# MSXII_SteeringWheelRightBoard.net
KiCad netlist of a schematic drawn in Altium Designer
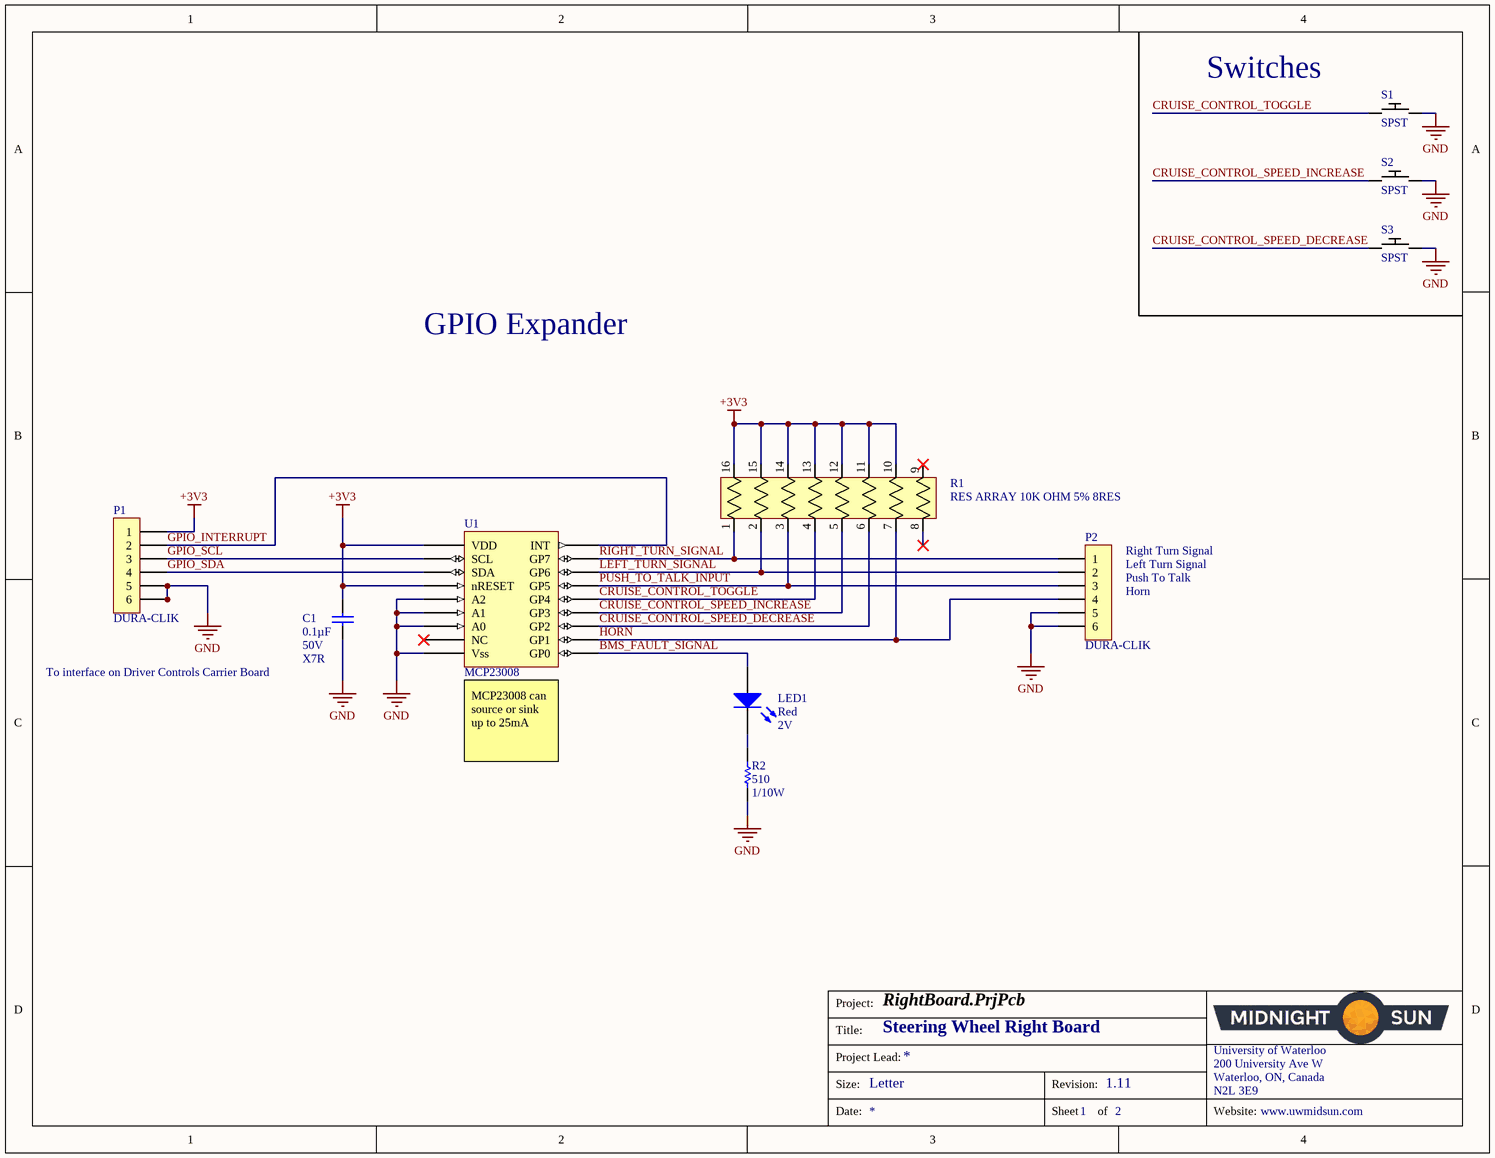
[diagram p0: MSXII_SteeringWheelRightBoard.SchDoc]

(export (version "E")
  (design (tool "Eeschema 10.0.6"))
  (components
    (comp (ref "C1")
      (value "CAP CER 0.1UF 50V 10% X7R 0603")
      (footprint "CAP, 0603")
      (description "0.10µF ±10% 50V Ceramic Capacitor X7R 0603 (1608 Metric)")
      (fields
        (field (name "TOLERANCE") "±10%")
        (field (name "CAPACITANCE") "0.1µF")
        (field (name "VOLTAGE") "50V")
        (field (name "TEMPERATURE COEFFICIENT") "X7R")
      )
      (libsource (lib "Schematic Diagrams") (part "CAP CER 0.1UF 50V 10% X7R 0603"))
    )
    (comp (ref "LED1")
      (value "LED RED CLEAR 2V 0603")
      (footprint "LED_0603")
      (description "Red 631nm LED Indication - Discrete 2V 0603 (1608 Metric)")
      (fields
        (field (name "MANUFACTURER") "Wurth Electronics Inc.")
        (field (name "MANUFACTURER PART NUMBER") "150060RS75000")
        (field (name "COLOR") "Red")
        (field (name "VOLTAGE - FORWARD (VF) (TYP)") "2V")
      )
      (libsource (lib "Schematic Diagrams") (part "LED RED CLEAR 2V 0603"))
    )
    (comp (ref "P1")
      (value "DURA-CLIK")
      (footprint "CONN, 6POS DURA-CLIK VERT")
      (description "6 Positions Header, Shrouded Connector 0.079\" (2.00mm) Surface Mount, Vertical Tin")
      (fields (field (name "MANUFACTURER") "Molex") (field (name "MANUFACTURER PART NUMBER") "5600200820"))
      (libsource (lib "") (part "CONN 6POS DURA-CLIK 0.079{dblquote}_1"))
    )
    (comp (ref "P2")
      (value "DURA-CLIK")
      (footprint "CONN, 6POS DURA-CLIK VERT")
      (description "6 Positions Header, Shrouded Connector 0.079\" (2.00mm) Surface Mount, Vertical Tin")
      (fields (field (name "MANUFACTURER") "Molex") (field (name "MANUFACTURER PART NUMBER") "5600200820"))
      (libsource (lib "Schematic Diagrams") (part "CONN 6POS DURA-CLIK 0.079{dblquote}"))
    )
    (comp (ref "R1")
      (value "RES ARRAY 10K OHM 5% 8RES")
      (footprint "RES ARRAY, 8 POS 1506")
      (description "RES ARRAY SMD 10K 5% 62.5mW 1506")
      (fields
        (field (name "MANUFACTURER_PART_NUMBER") "EXB-2HV103JV")
        (field (name "MANUFACTURER") "Panasonic Electronic Components")
        (field (name "COPYRIGHT") "Copyright (C) 2015 Accelerated Designs. All rights reserved")
      )
      (libsource (lib "Schematic Diagrams") (part "RES ARRAY 10K OHM 5% 8RES EXB-2HV103JV"))
    )
    (comp (ref "R2")
      (value "RES 510 OHM 5% 1/10W 0603")
      (footprint "RES, 0603")
      (description "RES SMD 510 OHM 5% 1/10W 0603")
      (fields
        (field (name "TOLERANCE") "±5%")
        (field (name "RESISTANCE") "510")
        (field (name "POWER") "1/10W")
      )
      (libsource (lib "Schematic Diagrams") (part "RES 510 OHM 5% 1/10W 0603"))
    )
    (comp (ref "S1")
      (value "SPST")
      (footprint "SW SPST D6 SERIES")
      (description "Pushbutton Switch SPST-NO Keyswitch Through Hole D6 Series")
      (fields (field (name "MANUFACTURER") "C&K") (field (name "MANUFACTURER PART NUMBER") "D6R00 F2 LFS"))
      (libsource (lib "Schematic Diagrams") (part "SW SPST-NO 0.1A 32V D6 Series"))
    )
    (comp (ref "S2")
      (value "SPST")
      (footprint "SW SPST D6 SERIES")
      (description "Pushbutton Switch SPST-NO Keyswitch Through Hole D6 Series")
      (fields (field (name "MANUFACTURER") "C&K") (field (name "MANUFACTURER PART NUMBER") "D6R00 F2 LFS"))
      (libsource (lib "Schematic Diagrams") (part "SW SPST-NO 0.1A 32V D6 Series"))
    )
    (comp (ref "S3")
      (value "SPST")
      (footprint "SW SPST D6 SERIES")
      (description "Pushbutton Switch SPST-NO Keyswitch Through Hole D6 Series")
      (fields (field (name "MANUFACTURER") "C&K") (field (name "MANUFACTURER PART NUMBER") "D6R00 F2 LFS"))
      (libsource (lib "Schematic Diagrams") (part "SW SPST-NO 0.1A 32V D6 Series"))
    )
    (comp (ref "U1")
      (value "MCP23008")
      (footprint "IC 18SOIC")
      (description "MCP23008 I/O Expander 8B+1Int 18P SOIC")
      (fields
        (field (name "MANUFACTURER") "Microchip Technology")
        (field (name "MANUFACTURER PART NUMBER") "MCP23008T-E/SO")
      )
      (libsource (lib "Schematic Diagrams") (part "IC I/O EXPANDER I2C 8B 18SOIC"))
    )
  )
  (nets
    (net (code "1") (name "+3V3") (class "Default")
      (node (ref "C1") (pin "1") (pinfunction "1_1") (pintype "passive"))
      (node (ref "P1") (pin "1") (pinfunction "1_1") (pintype "passive"))
      (node (ref "R1") (pin "10") (pinfunction "10_10") (pintype "passive"))
      (node (ref "R1") (pin "11") (pinfunction "11_11") (pintype "passive"))
      (node (ref "R1") (pin "12") (pinfunction "12_12") (pintype "passive"))
      (node (ref "R1") (pin "13") (pinfunction "13_13") (pintype "passive"))
      (node (ref "R1") (pin "14") (pinfunction "14_14") (pintype "passive"))
      (node (ref "R1") (pin "15") (pinfunction "15_15") (pintype "passive"))
      (node (ref "R1") (pin "16") (pinfunction "16_16") (pintype "passive"))
      (node (ref "U1") (pin "18") (pinfunction "VDD_18") (pintype "power_in"))
      (node (ref "U1") (pin "6") (pinfunction "nRESET_6") (pintype "input"))
    )
    (net (code "2") (name "/BMS_FAULT_SIGNAL") (class "Default")
      (node (ref "LED1") (pin "1") (pinfunction "A_1") (pintype "passive"))
      (node (ref "U1") (pin "10") (pinfunction "GP0_10") (pintype "bidirectional"))
    )
    (net (code "3") (name "/CRUISE_CONTROL_SPEED_DECREASE") (class "Default")
      (node (ref "R1") (pin "6") (pinfunction "6_6") (pintype "passive"))
      (node (ref "S3") (pin "1") (pinfunction "1_1") (pintype "passive"))
      (node (ref "U1") (pin "12") (pinfunction "GP2_12") (pintype "bidirectional"))
    )
    (net (code "4") (name "/CRUISE_CONTROL_SPEED_INCREASE") (class "Default")
      (node (ref "R1") (pin "5") (pinfunction "5_5") (pintype "passive"))
      (node (ref "S2") (pin "1") (pinfunction "1_1") (pintype "passive"))
      (node (ref "U1") (pin "13") (pinfunction "GP3_13") (pintype "bidirectional"))
    )
    (net (code "5") (name "/CRUISE_CONTROL_TOGGLE") (class "Default")
      (node (ref "R1") (pin "4") (pinfunction "4_4") (pintype "passive"))
      (node (ref "S1") (pin "1") (pinfunction "1_1") (pintype "passive"))
      (node (ref "U1") (pin "14") (pinfunction "GP4_14") (pintype "bidirectional"))
    )
    (net (code "6") (name "/GPIO_INTERRUPT") (class "Default")
      (node (ref "P1") (pin "2") (pinfunction "2_2") (pintype "passive"))
      (node (ref "U1") (pin "8") (pinfunction "INT_8") (pintype "output"))
    )
    (net (code "7") (name "/GPIO_SCL") (class "Default")
      (node (ref "P1") (pin "3") (pinfunction "3_3") (pintype "passive"))
      (node (ref "U1") (pin "1") (pinfunction "SCL_1") (pintype "bidirectional"))
    )
    (net (code "8") (name "/GPIO_SDA") (class "Default")
      (node (ref "P1") (pin "4") (pinfunction "4_4") (pintype "passive"))
      (node (ref "U1") (pin "2") (pinfunction "SDA_2") (pintype "bidirectional"))
    )
    (net (code "9") (name "/HORN") (class "Default")
      (node (ref "P2") (pin "4") (pinfunction "4_4") (pintype "passive"))
      (node (ref "R1") (pin "7") (pinfunction "7_7") (pintype "passive"))
      (node (ref "U1") (pin "11") (pinfunction "GP1_11") (pintype "bidirectional"))
    )
    (net (code "10") (name "/LEFT_TURN_SIGNAL") (class "Default")
      (node (ref "P2") (pin "2") (pinfunction "2_2") (pintype "passive"))
      (node (ref "R1") (pin "2") (pinfunction "2_2") (pintype "passive"))
      (node (ref "U1") (pin "16") (pinfunction "GP6_16") (pintype "bidirectional"))
    )
    (net (code "11") (name "/PUSH_TO_TALK_INPUT") (class "Default")
      (node (ref "P2") (pin "3") (pinfunction "3_3") (pintype "passive"))
      (node (ref "R1") (pin "3") (pinfunction "3_3") (pintype "passive"))
      (node (ref "U1") (pin "15") (pinfunction "GP5_15") (pintype "bidirectional"))
    )
    (net (code "12") (name "/RIGHT_TURN_SIGNAL") (class "Default")
      (node (ref "P2") (pin "1") (pinfunction "1_1") (pintype "passive"))
      (node (ref "R1") (pin "1") (pinfunction "1_1") (pintype "passive"))
      (node (ref "U1") (pin "17") (pinfunction "GP7_17") (pintype "bidirectional"))
    )
    (net (code "13") (name "GND") (class "Default")
      (node (ref "C1") (pin "2") (pinfunction "2_2") (pintype "passive"))
      (node (ref "P1") (pin "5") (pinfunction "5_5") (pintype "passive"))
      (node (ref "P1") (pin "6") (pinfunction "6_6") (pintype "passive"))
      (node (ref "P2") (pin "5") (pinfunction "5_5") (pintype "passive"))
      (node (ref "P2") (pin "6") (pinfunction "6_6") (pintype "passive"))
      (node (ref "R2") (pin "2") (pinfunction "2_2") (pintype "passive"))
      (node (ref "S1") (pin "2") (pinfunction "2_2") (pintype "passive"))
      (node (ref "S2") (pin "2") (pinfunction "2_2") (pintype "passive"))
      (node (ref "S3") (pin "2") (pinfunction "2_2") (pintype "passive"))
      (node (ref "U1") (pin "3") (pinfunction "A2_3") (pintype "input"))
      (node (ref "U1") (pin "4") (pinfunction "A1_4") (pintype "input"))
      (node (ref "U1") (pin "5") (pinfunction "A0_5") (pintype "input"))
      (node (ref "U1") (pin "9") (pinfunction "Vss_9") (pintype "power_in"))
    )
    (net (code "14") (name "Net-(LED1-K)") (class "Default")
      (node (ref "LED1") (pin "2") (pinfunction "K_2") (pintype "passive"))
      (node (ref "R2") (pin "1") (pinfunction "1_1") (pintype "passive"))
    )
    (net (code "15") (name "unconnected-(R1-Pad8)") (class "Default")
      (node (ref "R1") (pin "8") (pinfunction "8_8") (pintype "passive+no_connect"))
    )
    (net (code "16") (name "unconnected-(R1-Pad9)") (class "Default")
      (node (ref "R1") (pin "9") (pinfunction "9_9") (pintype "passive+no_connect"))
    )
    (net (code "17") (name "unconnected-(U1-NC-Pad7)") (class "Default")
      (node (ref "U1") (pin "7") (pinfunction "NC_7") (pintype "passive+no_connect"))
    )
  )
)
